# Servomoteur.net
KiCad netlist of a schematic drawn in Altium Designer
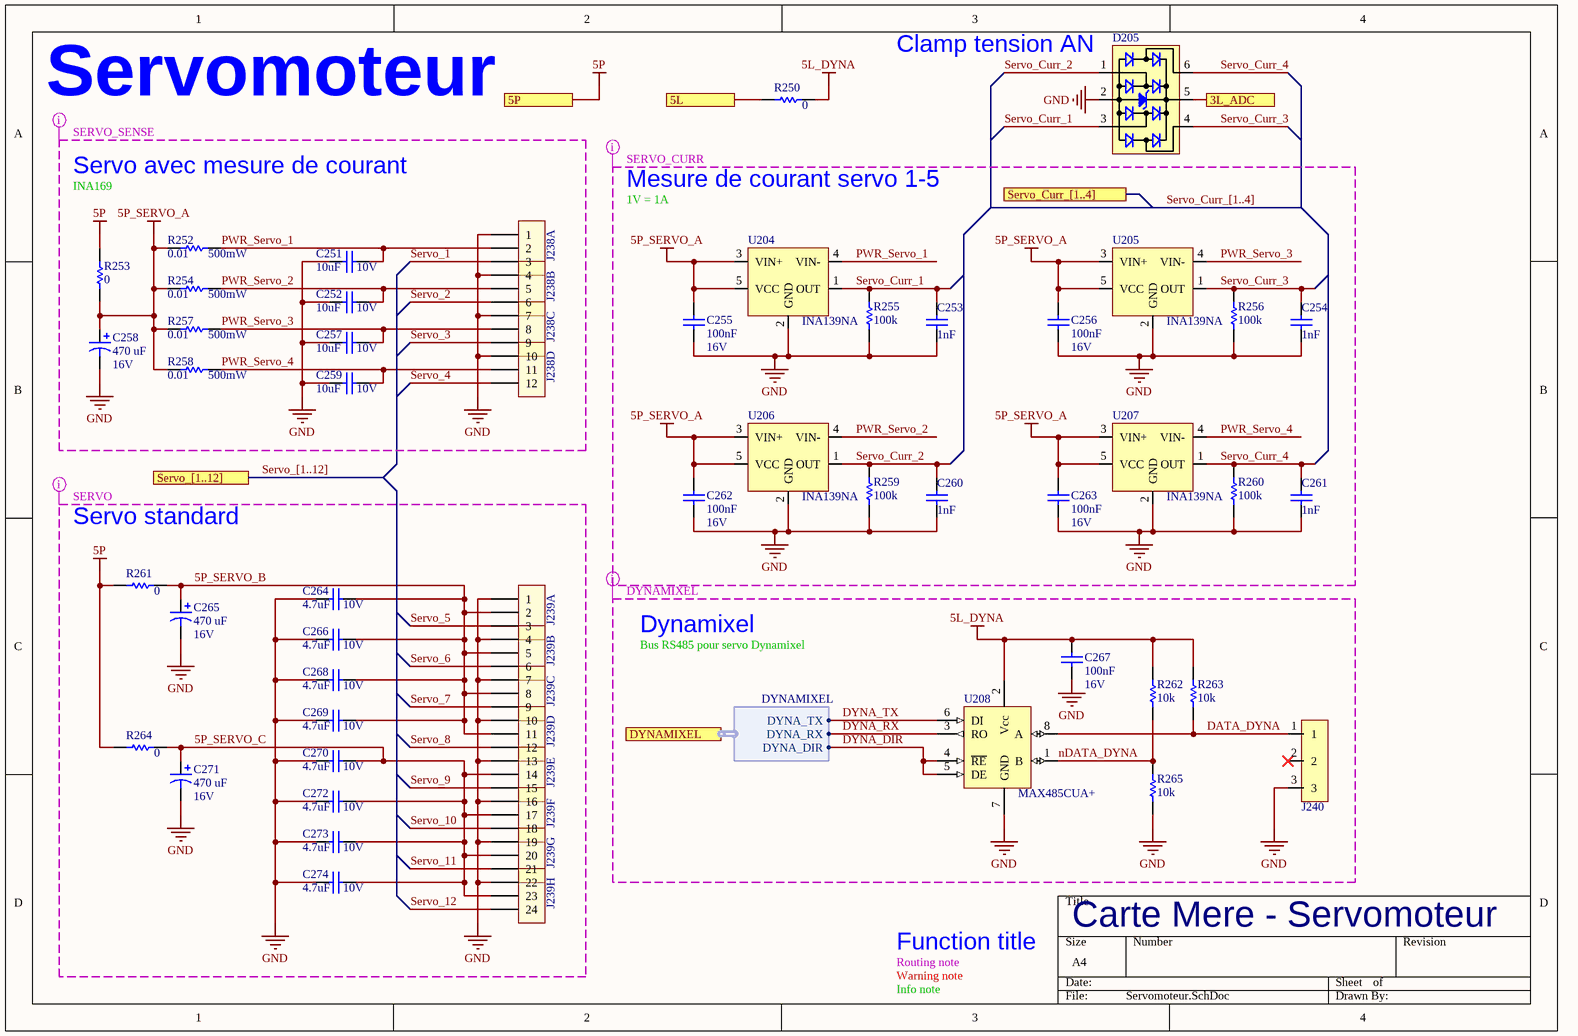
[diagram p0: Servomoteur.SchDoc]

(export (version "E")
  (design (tool "Eeschema 10.0.6"))
  (components
    (comp (ref "C251")
      (value "10uF")
      (footprint "WCAP-CSGP_0805, 2x1.25x1.25")
      (description "CAP CER 10uF 10V X7R 0805")
      (fields
        (field (name "MANUFACTURER") "Wurth Elektronik")
        (field (name "MANUFACTURER PART NUMBER") "885012207026")
        (field (name "RATEDVOLTAGE") "10V")
      )
      (libsource (lib "Condensateur") (part "WCAP-CSGP, 885012207026"))
    )
    (comp (ref "C252")
      (value "10uF")
      (footprint "WCAP-CSGP_0805, 2x1.25x1.25")
      (description "CAP CER 10uF 10V X7R 0805")
      (fields
        (field (name "MANUFACTURER") "Wurth Elektronik")
        (field (name "MANUFACTURER PART NUMBER") "885012207026")
        (field (name "RATEDVOLTAGE") "10V")
      )
      (libsource (lib "Condensateur") (part "WCAP-CSGP, 885012207026"))
    )
    (comp (ref "C253")
      (value "1nF")
      (footprint "WCAP-CSGP_0402, 1x0.5x0.5")
      (description "CAP CER 1nF 50V X7R 0402")
      (fields
        (field (name "MANUFACTURER") "Wurth Elektronik")
        (field (name "MANUFACTURER PART NUMBER") "885012205061")
      )
      (libsource (lib "Condensateur") (part "WCAP-CSGP, 885012205061"))
    )
    (comp (ref "C254")
      (value "1nF")
      (footprint "WCAP-CSGP_0402, 1x0.5x0.5")
      (description "CAP CER 1nF 50V X7R 0402")
      (fields
        (field (name "MANUFACTURER") "Wurth Elektronik")
        (field (name "MANUFACTURER PART NUMBER") "885012205061")
      )
      (libsource (lib "Condensateur") (part "WCAP-CSGP, 885012205061"))
    )
    (comp (ref "C255")
      (value "100nF")
      (footprint "WCAP-CSGP_0402, 1x0.5x0.5")
      (description "CAP CER 100nF 16V X7R 0402")
      (fields
        (field (name "MANUFACTURER") "Wurth Elektronik")
        (field (name "MANUFACTURER PART NUMBER") "885012205037")
        (field (name "RATEDVOLTAGE") "16V")
      )
      (libsource (lib "Condensateur") (part "WCAP-CSGP, 885012205037"))
    )
    (comp (ref "C256")
      (value "100nF")
      (footprint "WCAP-CSGP_0402, 1x0.5x0.5")
      (description "CAP CER 100nF 16V X7R 0402")
      (fields
        (field (name "MANUFACTURER") "Wurth Elektronik")
        (field (name "MANUFACTURER PART NUMBER") "885012205037")
        (field (name "RATEDVOLTAGE") "16V")
      )
      (libsource (lib "Condensateur") (part "WCAP-CSGP, 885012205037"))
    )
    (comp (ref "C257")
      (value "10uF")
      (footprint "WCAP-CSGP_0805, 2x1.25x1.25")
      (description "CAP CER 10uF 10V X7R 0805")
      (fields
        (field (name "MANUFACTURER") "Wurth Elektronik")
        (field (name "MANUFACTURER PART NUMBER") "885012207026")
        (field (name "RATEDVOLTAGE") "10V")
      )
      (libsource (lib "Condensateur") (part "WCAP-CSGP, 885012207026"))
    )
    (comp (ref "C258")
      (value "470 uF")
      (footprint "WCAP-ATG8_8x11.5x3.5x0.5")
      (description "CAP Alu 470 UF 20% 16 V")
      (fields
        (field (name "MANUFACTURER") "Wurth Elektronik")
        (field (name "MANUFACTURER PART NUMBER") "860010374012")
        (field (name "RATEDVOLTAGE") "16V")
      )
      (libsource (lib "Condensateur") (part "WCAP-ATG8, 860010374012"))
    )
    (comp (ref "C259")
      (value "10uF")
      (footprint "WCAP-CSGP_0805, 2x1.25x1.25")
      (description "CAP CER 10uF 10V X7R 0805")
      (fields
        (field (name "MANUFACTURER") "Wurth Elektronik")
        (field (name "MANUFACTURER PART NUMBER") "885012207026")
        (field (name "RATEDVOLTAGE") "10V")
      )
      (libsource (lib "Condensateur") (part "WCAP-CSGP, 885012207026"))
    )
    (comp (ref "C260")
      (value "1nF")
      (footprint "WCAP-CSGP_0402, 1x0.5x0.5")
      (description "CAP CER 1nF 50V X7R 0402")
      (fields
        (field (name "MANUFACTURER") "Wurth Elektronik")
        (field (name "MANUFACTURER PART NUMBER") "885012205061")
      )
      (libsource (lib "Condensateur") (part "WCAP-CSGP, 885012205061"))
    )
    (comp (ref "C261")
      (value "1nF")
      (footprint "WCAP-CSGP_0402, 1x0.5x0.5")
      (description "CAP CER 1nF 50V X7R 0402")
      (fields
        (field (name "MANUFACTURER") "Wurth Elektronik")
        (field (name "MANUFACTURER PART NUMBER") "885012205061")
      )
      (libsource (lib "Condensateur") (part "WCAP-CSGP, 885012205061"))
    )
    (comp (ref "C262")
      (value "100nF")
      (footprint "WCAP-CSGP_0402, 1x0.5x0.5")
      (description "CAP CER 100nF 16V X7R 0402")
      (fields
        (field (name "MANUFACTURER") "Wurth Elektronik")
        (field (name "MANUFACTURER PART NUMBER") "885012205037")
        (field (name "RATEDVOLTAGE") "16V")
      )
      (libsource (lib "Condensateur") (part "WCAP-CSGP, 885012205037"))
    )
    (comp (ref "C263")
      (value "100nF")
      (footprint "WCAP-CSGP_0402, 1x0.5x0.5")
      (description "CAP CER 100nF 16V X7R 0402")
      (fields
        (field (name "MANUFACTURER") "Wurth Elektronik")
        (field (name "MANUFACTURER PART NUMBER") "885012205037")
        (field (name "RATEDVOLTAGE") "16V")
      )
      (libsource (lib "Condensateur") (part "WCAP-CSGP, 885012205037"))
    )
    (comp (ref "C264")
      (value "4.7uF")
      (footprint "WCAP-CSGP_0603, 1.6x0.8x0.8")
      (description "CAP CER 4.7UF 10V X5R 0603")
      (fields
        (field (name "MANUFACTURER") "Wurth Elektronik")
        (field (name "MANUFACTURER PART NUMBER") "885012106012")
        (field (name "RATEDVOLTAGE") "10V")
      )
      (libsource (lib "Condensateur") (part "WCAP-CSGP, 885012106012"))
    )
    (comp (ref "C265")
      (value "470 uF")
      (footprint "WCAP-ATG8_8x11.5x3.5x0.5")
      (description "CAP Alu 470 UF 20% 16 V")
      (fields
        (field (name "MANUFACTURER") "Wurth Elektronik")
        (field (name "MANUFACTURER PART NUMBER") "860010374012")
        (field (name "RATEDVOLTAGE") "16V")
      )
      (libsource (lib "Condensateur") (part "WCAP-ATG8, 860010374012"))
    )
    (comp (ref "C266")
      (value "4.7uF")
      (footprint "WCAP-CSGP_0603, 1.6x0.8x0.8")
      (description "CAP CER 4.7UF 10V X5R 0603")
      (fields
        (field (name "MANUFACTURER") "Wurth Elektronik")
        (field (name "MANUFACTURER PART NUMBER") "885012106012")
        (field (name "RATEDVOLTAGE") "10V")
      )
      (libsource (lib "Condensateur") (part "WCAP-CSGP, 885012106012"))
    )
    (comp (ref "C267")
      (value "100nF")
      (footprint "WCAP-CSGP_0402, 1x0.5x0.5")
      (description "CAP CER 100nF 16V X7R 0402")
      (fields
        (field (name "MANUFACTURER") "Wurth Elektronik")
        (field (name "MANUFACTURER PART NUMBER") "885012205037")
        (field (name "RATEDVOLTAGE") "16V")
      )
      (libsource (lib "Condensateur") (part "WCAP-CSGP, 885012205037"))
    )
    (comp (ref "C268")
      (value "4.7uF")
      (footprint "WCAP-CSGP_0603, 1.6x0.8x0.8")
      (description "CAP CER 4.7UF 10V X5R 0603")
      (fields
        (field (name "MANUFACTURER") "Wurth Elektronik")
        (field (name "MANUFACTURER PART NUMBER") "885012106012")
        (field (name "RATEDVOLTAGE") "10V")
      )
      (libsource (lib "Condensateur") (part "WCAP-CSGP, 885012106012"))
    )
    (comp (ref "C269")
      (value "4.7uF")
      (footprint "WCAP-CSGP_0603, 1.6x0.8x0.8")
      (description "CAP CER 4.7UF 10V X5R 0603")
      (fields
        (field (name "MANUFACTURER") "Wurth Elektronik")
        (field (name "MANUFACTURER PART NUMBER") "885012106012")
        (field (name "RATEDVOLTAGE") "10V")
      )
      (libsource (lib "Condensateur") (part "WCAP-CSGP, 885012106012"))
    )
    (comp (ref "C270")
      (value "4.7uF")
      (footprint "WCAP-CSGP_0603, 1.6x0.8x0.8")
      (description "CAP CER 4.7UF 10V X5R 0603")
      (fields
        (field (name "MANUFACTURER") "Wurth Elektronik")
        (field (name "MANUFACTURER PART NUMBER") "885012106012")
        (field (name "RATEDVOLTAGE") "10V")
      )
      (libsource (lib "Condensateur") (part "WCAP-CSGP, 885012106012"))
    )
    (comp (ref "C271")
      (value "470 uF")
      (footprint "WCAP-ATG8_8x11.5x3.5x0.5")
      (description "CAP Alu 470 UF 20% 16 V")
      (fields
        (field (name "MANUFACTURER") "Wurth Elektronik")
        (field (name "MANUFACTURER PART NUMBER") "860010374012")
        (field (name "RATEDVOLTAGE") "16V")
      )
      (libsource (lib "Condensateur") (part "WCAP-ATG8, 860010374012"))
    )
    (comp (ref "C272")
      (value "4.7uF")
      (footprint "WCAP-CSGP_0603, 1.6x0.8x0.8")
      (description "CAP CER 4.7UF 10V X5R 0603")
      (fields
        (field (name "MANUFACTURER") "Wurth Elektronik")
        (field (name "MANUFACTURER PART NUMBER") "885012106012")
        (field (name "RATEDVOLTAGE") "10V")
      )
      (libsource (lib "Condensateur") (part "WCAP-CSGP, 885012106012"))
    )
    (comp (ref "C273")
      (value "4.7uF")
      (footprint "WCAP-CSGP_0603, 1.6x0.8x0.8")
      (description "CAP CER 4.7UF 10V X5R 0603")
      (fields
        (field (name "MANUFACTURER") "Wurth Elektronik")
        (field (name "MANUFACTURER PART NUMBER") "885012106012")
        (field (name "RATEDVOLTAGE") "10V")
      )
      (libsource (lib "Condensateur") (part "WCAP-CSGP, 885012106012"))
    )
    (comp (ref "C274")
      (value "4.7uF")
      (footprint "WCAP-CSGP_0603, 1.6x0.8x0.8")
      (description "CAP CER 4.7UF 10V X5R 0603")
      (fields
        (field (name "MANUFACTURER") "Wurth Elektronik")
        (field (name "MANUFACTURER PART NUMBER") "885012106012")
        (field (name "RATEDVOLTAGE") "10V")
      )
      (libsource (lib "Condensateur") (part "WCAP-CSGP, 885012106012"))
    )
    (comp (ref "D205")
      (value "824001")
      (footprint "SOT-23-6L")
      (description "WE-TVS TVS Diode 4+1Ch 5V SOT23-6L")
      (fields (field (name "MANUFACTURER") "Wurth Elektronik"))
      (libsource (lib "Diode") (part "824001"))
    )
    (comp (ref "J238")
      (value "TSW-104-08-F-T-RA")
      (footprint "TSW-104-08-F-T-RA")
      (description "CONN HEADER R/A 3L x 4POS 2.54MM")
      (fields (field (name "MANUFACTURER") "SAMTEC"))
      (libsource (lib "Connecteurs") (part "TSW-104-08-F-T-RA"))
    )
    (comp (ref "J239")
      (value "TSW-104-08-F-T-RA")
      (footprint "TSW-108-08-F-T-RA")
      (description "CONN HEADER R/A 3L x 8POS 2.54MM")
      (fields (field (name "MANUFACTURER") "SAMTEC"))
      (libsource (lib "Connecteurs") (part "TSW-108-08-F-T-RA"))
    )
    (comp (ref "J240")
      (value "22-03-5035")
      (footprint "20-03-5035")
      (description "CONN HEADER VERT 3POS 2.5MM")
      (fields (field (name "MANUFACTURER") "MOLEX"))
      (libsource (lib "Connecteurs") (part "20-03-5035"))
    )
    (comp (ref "R250")
      (value "0")
      (footprint "RESC1608X06N")
      (description "RES SMD 0 OHM 1% 1/10W 0603")
      (fields
        (field (name "MANUFACTURER") "Yageo")
        (field (name "MANUFACTURER PART NUMBER") "RC0603FR-070RL")
      )
      (libsource (lib "Resistance") (part "RC0603FR-070RL"))
    )
    (comp (ref "R252")
      (value "0.01")
      (footprint "RESC2012X06N")
      (description "RES 0.01 OHM 1% 500mW 0805")
      (fields
        (field (name "MANUFACTURER") "Bourns")
        (field (name "MANUFACTURER PART NUMBER") "CRF0805-FZ-R010ELF")
        (field (name "POWER") "500mW")
      )
      (libsource (lib "Resistance") (part "CRF0805-FZ-R010ELF"))
    )
    (comp (ref "R253")
      (value "0")
      (footprint "RESC1608X06N")
      (description "RES SMD 0 OHM 1% 1/10W 0603")
      (fields
        (field (name "MANUFACTURER") "Yageo")
        (field (name "MANUFACTURER PART NUMBER") "RC0603FR-070RL")
      )
      (libsource (lib "Resistance") (part "RC0603FR-070RL"))
    )
    (comp (ref "R254")
      (value "0.01")
      (footprint "RESC2012X06N")
      (description "RES 0.01 OHM 1% 500mW 0805")
      (fields
        (field (name "MANUFACTURER") "Bourns")
        (field (name "MANUFACTURER PART NUMBER") "CRF0805-FZ-R010ELF")
        (field (name "POWER") "500mW")
      )
      (libsource (lib "Resistance") (part "CRF0805-FZ-R010ELF"))
    )
    (comp (ref "R255")
      (value "100k")
      (footprint "RESC1005X04N")
      (description "RES SMD 100K OHM 1% 1/16W 0402")
      (fields (field (name "POWER") "63mW") (field (name "MANUFACTURER") "Yageo"))
      (libsource (lib "Resistance") (part "RC0402FR-07100KL"))
    )
    (comp (ref "R256")
      (value "100k")
      (footprint "RESC1005X04N")
      (description "RES SMD 100K OHM 1% 1/16W 0402")
      (fields (field (name "POWER") "63mW") (field (name "MANUFACTURER") "Yageo"))
      (libsource (lib "Resistance") (part "RC0402FR-07100KL"))
    )
    (comp (ref "R257")
      (value "0.01")
      (footprint "RESC2012X06N")
      (description "RES 0.01 OHM 1% 500mW 0805")
      (fields
        (field (name "MANUFACTURER") "Bourns")
        (field (name "MANUFACTURER PART NUMBER") "CRF0805-FZ-R010ELF")
        (field (name "POWER") "500mW")
      )
      (libsource (lib "Resistance") (part "CRF0805-FZ-R010ELF"))
    )
    (comp (ref "R258")
      (value "0.01")
      (footprint "RESC2012X06N")
      (description "RES 0.01 OHM 1% 500mW 0805")
      (fields
        (field (name "MANUFACTURER") "Bourns")
        (field (name "MANUFACTURER PART NUMBER") "CRF0805-FZ-R010ELF")
        (field (name "POWER") "500mW")
      )
      (libsource (lib "Resistance") (part "CRF0805-FZ-R010ELF"))
    )
    (comp (ref "R259")
      (value "100k")
      (footprint "RESC1005X04N")
      (description "RES SMD 100K OHM 1% 1/16W 0402")
      (fields (field (name "POWER") "63mW") (field (name "MANUFACTURER") "Yageo"))
      (libsource (lib "Resistance") (part "RC0402FR-07100KL"))
    )
    (comp (ref "R260")
      (value "100k")
      (footprint "RESC1005X04N")
      (description "RES SMD 100K OHM 1% 1/16W 0402")
      (fields (field (name "POWER") "63mW") (field (name "MANUFACTURER") "Yageo"))
      (libsource (lib "Resistance") (part "RC0402FR-07100KL"))
    )
    (comp (ref "R261")
      (value "0")
      (footprint "RESC1608X06N")
      (description "RES SMD 0 OHM 1% 1/10W 0603")
      (fields
        (field (name "MANUFACTURER") "Yageo")
        (field (name "MANUFACTURER PART NUMBER") "RC0603FR-070RL")
      )
      (libsource (lib "Resistance") (part "RC0603FR-070RL"))
    )
    (comp (ref "R262")
      (value "10k")
      (footprint "RESC1005X04N")
      (description "RES SMD 10K OHM 1% 1/16W 0402")
      (fields (field (name "POWER") "63mW") (field (name "MANUFACTURER") "Yageo"))
      (libsource (lib "Resistance") (part "RC0402FR-0710KL"))
    )
    (comp (ref "R263")
      (value "10k")
      (footprint "RESC1005X04N")
      (description "RES SMD 10K OHM 1% 1/16W 0402")
      (fields (field (name "POWER") "63mW") (field (name "MANUFACTURER") "Yageo"))
      (libsource (lib "Resistance") (part "RC0402FR-0710KL"))
    )
    (comp (ref "R264")
      (value "0")
      (footprint "RESC1608X06N")
      (description "RES SMD 0 OHM 1% 1/10W 0603")
      (fields
        (field (name "MANUFACTURER") "Yageo")
        (field (name "MANUFACTURER PART NUMBER") "RC0603FR-070RL")
      )
      (libsource (lib "Resistance") (part "RC0603FR-070RL"))
    )
    (comp (ref "R265")
      (value "10k")
      (footprint "RESC1005X04N")
      (description "RES SMD 10K OHM 1% 1/16W 0402")
      (fields (field (name "POWER") "63mW") (field (name "MANUFACTURER") "Yageo"))
      (libsource (lib "Resistance") (part "RC0402FR-0710KL"))
    )
    (comp (ref "U204")
      (value "INA139NA")
      (footprint "SOT23_95P280X145-5N")
      (description "IC CURRENT MONITOR 0.5% SOT23-5")
      (fields (field (name "MANUFACTURER") "Texas Instruments"))
      (libsource (lib "CI") (part "INA139NA"))
    )
    (comp (ref "U205")
      (value "INA139NA")
      (footprint "SOT23_95P280X145-5N")
      (description "IC CURRENT MONITOR 0.5% SOT23-5")
      (fields (field (name "MANUFACTURER") "Texas Instruments"))
      (libsource (lib "CI") (part "INA139NA"))
    )
    (comp (ref "U206")
      (value "INA139NA")
      (footprint "SOT23_95P280X145-5N")
      (description "IC CURRENT MONITOR 0.5% SOT23-5")
      (fields (field (name "MANUFACTURER") "Texas Instruments"))
      (libsource (lib "CI") (part "INA139NA"))
    )
    (comp (ref "U207")
      (value "INA139NA")
      (footprint "SOT23_95P280X145-5N")
      (description "IC CURRENT MONITOR 0.5% SOT23-5")
      (fields (field (name "MANUFACTURER") "Texas Instruments"))
      (libsource (lib "CI") (part "INA139NA"))
    )
    (comp (ref "U208")
      (value "MAX485CUA+")
      (footprint "MSOP-8")
      (description "IC TXRX RS485/RS422 8-UMAX")
      (fields (field (name "MANUFACTURER") "Maxim Integrated"))
      (libsource (lib "CI") (part "MAX485CUA+"))
    )
  )
  (nets
    (net (code "2") (name "/3L_ADC") (class "Default") (node (ref "D205") (pin "5") (pintype "passive")))
    (net (code "3") (name "/5L") (class "Default")
      (node (ref "R250") (pin "1") (pinfunction "1_1") (pintype "passive"))
    )
    (net (code "4") (name "/5P_SERVO_B") (class "Default")
      (node (ref "C264") (pin "1") (pinfunction "1_1") (pintype "passive"))
      (node (ref "C265") (pin "1") (pinfunction "1_1") (pintype "passive"))
      (node (ref "C266") (pin "1") (pinfunction "1_1") (pintype "passive"))
      (node (ref "C268") (pin "1") (pinfunction "1_1") (pintype "passive"))
      (node (ref "C269") (pin "1") (pinfunction "1_1") (pintype "passive"))
      (node (ref "J239") (pin "11") (pinfunction "11_11") (pintype "passive"))
      (node (ref "J239") (pin "2") (pinfunction "2_2") (pintype "passive"))
      (node (ref "J239") (pin "5") (pinfunction "5_5") (pintype "passive"))
      (node (ref "J239") (pin "8") (pinfunction "8_8") (pintype "passive"))
      (node (ref "R261") (pin "2") (pinfunction "2_2") (pintype "passive"))
    )
    (net (code "5") (name "/5P_SERVO_C") (class "Default")
      (node (ref "C270") (pin "1") (pinfunction "1_1") (pintype "passive"))
      (node (ref "C271") (pin "1") (pinfunction "1_1") (pintype "passive"))
      (node (ref "C272") (pin "1") (pinfunction "1_1") (pintype "passive"))
      (node (ref "C273") (pin "1") (pinfunction "1_1") (pintype "passive"))
      (node (ref "C274") (pin "1") (pinfunction "1_1") (pintype "passive"))
      (node (ref "J239") (pin "14") (pinfunction "14_14") (pintype "passive"))
      (node (ref "J239") (pin "17") (pinfunction "17_17") (pintype "passive"))
      (node (ref "J239") (pin "20") (pinfunction "20_20") (pintype "passive"))
      (node (ref "J239") (pin "23") (pinfunction "23_23") (pintype "passive"))
      (node (ref "R264") (pin "2") (pinfunction "2_2") (pintype "passive"))
    )
    (net (code "6") (name "/DATA_DYNA") (class "Default")
      (node (ref "J240") (pin "1") (pinfunction "1_1") (pintype "passive"))
      (node (ref "R263") (pin "1") (pinfunction "1_1") (pintype "passive"))
      (node (ref "U208") (pin "8") (pinfunction "A_8") (pintype "bidirectional"))
    )
    (net (code "7") (name "/DYNA_DIR") (class "Default")
      (node (ref "U208") (pin "4") (pinfunction "RE_4") (pintype "input"))
      (node (ref "U208") (pin "5") (pinfunction "DE_5") (pintype "input"))
    )
    (net (code "8") (name "/DYNA_RX") (class "Default")
      (node (ref "U208") (pin "3") (pinfunction "RO_3") (pintype "output"))
    )
    (net (code "9") (name "/DYNA_TX") (class "Default")
      (node (ref "U208") (pin "6") (pinfunction "DI_6") (pintype "input"))
    )
    (net (code "10") (name "/PWR_Servo_1") (class "Default")
      (node (ref "C251") (pin "2") (pinfunction "2_2") (pintype "passive"))
      (node (ref "J238") (pin "2") (pinfunction "2_2") (pintype "passive"))
      (node (ref "R252") (pin "2") (pinfunction "2_2") (pintype "passive"))
      (node (ref "U204") (pin "4") (pinfunction "VIN-_4") (pintype "passive"))
    )
    (net (code "11") (name "/PWR_Servo_2") (class "Default")
      (node (ref "C252") (pin "2") (pinfunction "2_2") (pintype "passive"))
      (node (ref "J238") (pin "5") (pinfunction "5_5") (pintype "passive"))
      (node (ref "R254") (pin "2") (pinfunction "2_2") (pintype "passive"))
      (node (ref "U206") (pin "4") (pinfunction "VIN-_4") (pintype "passive"))
    )
    (net (code "12") (name "/PWR_Servo_3") (class "Default")
      (node (ref "C257") (pin "2") (pinfunction "2_2") (pintype "passive"))
      (node (ref "J238") (pin "8") (pinfunction "8_8") (pintype "passive"))
      (node (ref "R257") (pin "2") (pinfunction "2_2") (pintype "passive"))
      (node (ref "U205") (pin "4") (pinfunction "VIN-_4") (pintype "passive"))
    )
    (net (code "13") (name "/PWR_Servo_4") (class "Default")
      (node (ref "C259") (pin "2") (pinfunction "2_2") (pintype "passive"))
      (node (ref "J238") (pin "11") (pinfunction "11_11") (pintype "passive"))
      (node (ref "R258") (pin "2") (pinfunction "2_2") (pintype "passive"))
      (node (ref "U207") (pin "4") (pinfunction "VIN-_4") (pintype "passive"))
    )
    (net (code "14") (name "/Servo_1") (class "Default")
      (node (ref "J238") (pin "3") (pinfunction "3_3") (pintype "passive"))
    )
    (net (code "15") (name "/Servo_2") (class "Default")
      (node (ref "J238") (pin "6") (pinfunction "6_6") (pintype "passive"))
    )
    (net (code "16") (name "/Servo_3") (class "Default")
      (node (ref "J238") (pin "9") (pinfunction "9_9") (pintype "passive"))
    )
    (net (code "17") (name "/Servo_4") (class "Default")
      (node (ref "J238") (pin "12") (pinfunction "12_12") (pintype "passive"))
    )
    (net (code "18") (name "/Servo_5") (class "Default")
      (node (ref "J239") (pin "3") (pinfunction "3_3") (pintype "passive"))
    )
    (net (code "19") (name "/Servo_6") (class "Default")
      (node (ref "J239") (pin "6") (pinfunction "6_6") (pintype "passive"))
    )
    (net (code "20") (name "/Servo_7") (class "Default")
      (node (ref "J239") (pin "9") (pinfunction "9_9") (pintype "passive"))
    )
    (net (code "21") (name "/Servo_8") (class "Default")
      (node (ref "J239") (pin "12") (pinfunction "12_12") (pintype "passive"))
    )
    (net (code "22") (name "/Servo_9") (class "Default")
      (node (ref "J239") (pin "15") (pinfunction "15_15") (pintype "passive"))
    )
    (net (code "23") (name "/Servo_10") (class "Default")
      (node (ref "J239") (pin "18") (pinfunction "18_18") (pintype "passive"))
    )
    (net (code "24") (name "/Servo_11") (class "Default")
      (node (ref "J239") (pin "21") (pinfunction "21_21") (pintype "passive"))
    )
    (net (code "25") (name "/Servo_12") (class "Default")
      (node (ref "J239") (pin "24") (pinfunction "24_24") (pintype "passive"))
    )
    (net (code "26") (name "/Servo_Curr_1") (class "Default")
      (node (ref "C253") (pin "1") (pinfunction "1_1") (pintype "passive"))
      (node (ref "D205") (pin "3") (pintype "passive"))
      (node (ref "R255") (pin "1") (pinfunction "1_1") (pintype "passive"))
      (node (ref "U204") (pin "1") (pinfunction "OUT_1") (pintype "passive"))
    )
    (net (code "27") (name "/Servo_Curr_2") (class "Default")
      (node (ref "C260") (pin "1") (pinfunction "1_1") (pintype "passive"))
      (node (ref "D205") (pin "1") (pintype "passive"))
      (node (ref "R259") (pin "1") (pinfunction "1_1") (pintype "passive"))
      (node (ref "U206") (pin "1") (pinfunction "OUT_1") (pintype "passive"))
    )
    (net (code "28") (name "/Servo_Curr_3") (class "Default")
      (node (ref "C254") (pin "1") (pinfunction "1_1") (pintype "passive"))
      (node (ref "D205") (pin "4") (pintype "passive"))
      (node (ref "R256") (pin "1") (pinfunction "1_1") (pintype "passive"))
      (node (ref "U205") (pin "1") (pinfunction "OUT_1") (pintype "passive"))
    )
    (net (code "29") (name "/Servo_Curr_4") (class "Default")
      (node (ref "C261") (pin "1") (pinfunction "1_1") (pintype "passive"))
      (node (ref "D205") (pin "6") (pintype "passive"))
      (node (ref "R260") (pin "1") (pinfunction "1_1") (pintype "passive"))
      (node (ref "U207") (pin "1") (pinfunction "OUT_1") (pintype "passive"))
    )
    (net (code "32") (name "/nDATA_DYNA") (class "Default")
      (node (ref "R262") (pin "1") (pinfunction "1_1") (pintype "passive"))
      (node (ref "R265") (pin "2") (pinfunction "2_2") (pintype "passive"))
      (node (ref "U208") (pin "1") (pinfunction "B_1") (pintype "bidirectional"))
    )
    (net (code "34") (name "5L_DYNA") (class "Default")
      (node (ref "C267") (pin "1") (pinfunction "1_1") (pintype "passive"))
      (node (ref "R250") (pin "2") (pinfunction "2_2") (pintype "passive"))
      (node (ref "R262") (pin "2") (pinfunction "2_2") (pintype "passive"))
      (node (ref "R263") (pin "2") (pinfunction "2_2") (pintype "passive"))
      (node (ref "U208") (pin "2") (pinfunction "Vcc_2") (pintype "power_in"))
    )
    (net (code "35") (name "5P") (class "Default")
      (node (ref "R253") (pin "1") (pinfunction "1_1") (pintype "passive"))
      (node (ref "R261") (pin "1") (pinfunction "1_1") (pintype "passive"))
      (node (ref "R264") (pin "1") (pinfunction "1_1") (pintype "passive"))
    )
    (net (code "36") (name "5P_SERVO_A") (class "Default")
      (node (ref "C255") (pin "1") (pinfunction "1_1") (pintype "passive"))
      (node (ref "C256") (pin "1") (pinfunction "1_1") (pintype "passive"))
      (node (ref "C258") (pin "1") (pinfunction "1_1") (pintype "passive"))
      (node (ref "C262") (pin "1") (pinfunction "1_1") (pintype "passive"))
      (node (ref "C263") (pin "1") (pinfunction "1_1") (pintype "passive"))
      (node (ref "R252") (pin "1") (pinfunction "1_1") (pintype "passive"))
      (node (ref "R253") (pin "2") (pinfunction "2_2") (pintype "passive"))
      (node (ref "R254") (pin "1") (pinfunction "1_1") (pintype "passive"))
      (node (ref "R257") (pin "1") (pinfunction "1_1") (pintype "passive"))
      (node (ref "R258") (pin "1") (pinfunction "1_1") (pintype "passive"))
      (node (ref "U204") (pin "3") (pinfunction "VIN+_3") (pintype "passive"))
      (node (ref "U204") (pin "5") (pinfunction "VCC_5") (pintype "passive"))
      (node (ref "U205") (pin "3") (pinfunction "VIN+_3") (pintype "passive"))
      (node (ref "U205") (pin "5") (pinfunction "VCC_5") (pintype "passive"))
      (node (ref "U206") (pin "3") (pinfunction "VIN+_3") (pintype "passive"))
      (node (ref "U206") (pin "5") (pinfunction "VCC_5") (pintype "passive"))
      (node (ref "U207") (pin "3") (pinfunction "VIN+_3") (pintype "passive"))
      (node (ref "U207") (pin "5") (pinfunction "VCC_5") (pintype "passive"))
    )
    (net (code "37") (name "GND") (class "Default")
      (node (ref "C251") (pin "1") (pinfunction "1_1") (pintype "passive"))
      (node (ref "C252") (pin "1") (pinfunction "1_1") (pintype "passive"))
      (node (ref "C253") (pin "2") (pinfunction "2_2") (pintype "passive"))
      (node (ref "C254") (pin "2") (pinfunction "2_2") (pintype "passive"))
      (node (ref "C255") (pin "2") (pinfunction "2_2") (pintype "passive"))
      (node (ref "C256") (pin "2") (pinfunction "2_2") (pintype "passive"))
      (node (ref "C257") (pin "1") (pinfunction "1_1") (pintype "passive"))
      (node (ref "C258") (pin "2") (pinfunction "2_2") (pintype "passive"))
      (node (ref "C259") (pin "1") (pinfunction "1_1") (pintype "passive"))
      (node (ref "C260") (pin "2") (pinfunction "2_2") (pintype "passive"))
      (node (ref "C261") (pin "2") (pinfunction "2_2") (pintype "passive"))
      (node (ref "C262") (pin "2") (pinfunction "2_2") (pintype "passive"))
      (node (ref "C263") (pin "2") (pinfunction "2_2") (pintype "passive"))
      (node (ref "C264") (pin "2") (pinfunction "2_2") (pintype "passive"))
      (node (ref "C265") (pin "2") (pinfunction "2_2") (pintype "passive"))
      (node (ref "C266") (pin "2") (pinfunction "2_2") (pintype "passive"))
      (node (ref "C267") (pin "2") (pinfunction "2_2") (pintype "passive"))
      (node (ref "C268") (pin "2") (pinfunction "2_2") (pintype "passive"))
      (node (ref "C269") (pin "2") (pinfunction "2_2") (pintype "passive"))
      (node (ref "C270") (pin "2") (pinfunction "2_2") (pintype "passive"))
      (node (ref "C271") (pin "2") (pinfunction "2_2") (pintype "passive"))
      (node (ref "C272") (pin "2") (pinfunction "2_2") (pintype "passive"))
      (node (ref "C273") (pin "2") (pinfunction "2_2") (pintype "passive"))
      (node (ref "C274") (pin "2") (pinfunction "2_2") (pintype "passive"))
      (node (ref "D205") (pin "2") (pintype "passive"))
      (node (ref "J238") (pin "1") (pinfunction "1_1") (pintype "passive"))
      (node (ref "J238") (pin "10") (pinfunction "10_10") (pintype "passive"))
      (node (ref "J238") (pin "4") (pinfunction "4_4") (pintype "passive"))
      (node (ref "J238") (pin "7") (pinfunction "7_7") (pintype "passive"))
      (node (ref "J239") (pin "1") (pinfunction "1_1") (pintype "passive"))
      (node (ref "J239") (pin "10") (pinfunction "10_10") (pintype "passive"))
      (node (ref "J239") (pin "13") (pinfunction "13_13") (pintype "passive"))
      (node (ref "J239") (pin "16") (pinfunction "16_16") (pintype "passive"))
      (node (ref "J239") (pin "19") (pinfunction "19_19") (pintype "passive"))
      (node (ref "J239") (pin "22") (pinfunction "22_22") (pintype "passive"))
      (node (ref "J239") (pin "4") (pinfunction "4_4") (pintype "passive"))
      (node (ref "J239") (pin "7") (pinfunction "7_7") (pintype "passive"))
      (node (ref "J240") (pin "3") (pinfunction "3_3") (pintype "passive"))
      (node (ref "R255") (pin "2") (pinfunction "2_2") (pintype "passive"))
      (node (ref "R256") (pin "2") (pinfunction "2_2") (pintype "passive"))
      (node (ref "R259") (pin "2") (pinfunction "2_2") (pintype "passive"))
      (node (ref "R260") (pin "2") (pinfunction "2_2") (pintype "passive"))
      (node (ref "R265") (pin "1") (pinfunction "1_1") (pintype "passive"))
      (node (ref "U204") (pin "2") (pinfunction "GND_2") (pintype "passive"))
      (node (ref "U205") (pin "2") (pinfunction "GND_2") (pintype "passive"))
      (node (ref "U206") (pin "2") (pinfunction "GND_2") (pintype "passive"))
      (node (ref "U207") (pin "2") (pinfunction "GND_2") (pintype "passive"))
      (node (ref "U208") (pin "7") (pinfunction "GND_7") (pintype "power_in"))
    )
    (net (code "38") (name "unconnected-(J240-Pad2)") (class "Default")
      (node (ref "J240") (pin "2") (pinfunction "2_2") (pintype "passive+no_connect"))
    )
  )
)
